# motor_schematic.net
KiCad netlist of a schematic drawn in EAGLE
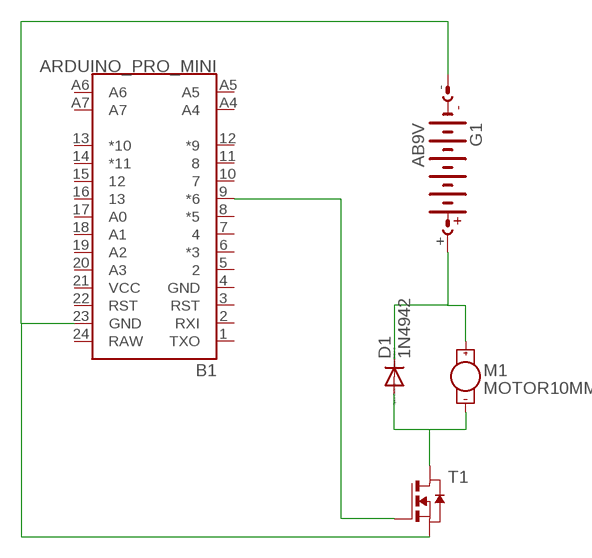
[diagram p0: schematic, sheet 1]

(export (version "E")
  (design (tool "Eeschema 10.0.6"))
  (components
    (comp (ref "B1")
      (value "ARDUINO_PRO_MINI")
      (footprint "eagle-import:ARDUINO_PRO_MINI")
      (libsource (lib "eagle-import") (part "ARDUINO_PRO_MINI"))
    )
    (comp (ref "D1")
      (value "1N4942")
      (footprint "eagle-import:DO41-10")
      (libsource (lib "eagle-import") (part "1N4942"))
    )
    (comp (ref "G1")
      (value "AB9V")
      (footprint "eagle-import:AB9V")
      (libsource (lib "eagle-import") (part "AB9V"))
    )
    (comp (ref "M1")
      (value "MOTOR10MM")
      (footprint "eagle-import:VIBE-MOTOR-10MM")
      (libsource (lib "eagle-import") (part "MOTOR10MM"))
    )
    (comp (ref "T1")
      (value "NMOSSOT23")
      (footprint "eagle-import:SOT-23")
      (libsource (lib "eagle-import") (part "NMOSSOT23"))
    )
  )
  (nets
    (net (code "1") (name "/GND") (class "Default")
      (node (ref "B1") (pin "4") (pinfunction "GND_4") (pintype "power_in"))
    )
    (net (code "2") (name "/RAW") (class "Default")
      (node (ref "B1") (pin "24") (pinfunction "RAW_24") (pintype "power_in"))
    )
    (net (code "3") (name "/VCC") (class "Default")
      (node (ref "B1") (pin "21") (pinfunction "VCC_21") (pintype "power_in"))
    )
    (net (code "4") (name "Net-(B1-*6)") (class "Default")
      (node (ref "B1") (pin "9") (pinfunction "*6_9") (pintype "bidirectional"))
      (node (ref "T1") (pin "3") (pinfunction "G_3") (pintype "passive"))
    )
    (net (code "5") (name "Net-(D1-PadC)") (class "Default")
      (node (ref "D1") (pin "C") (pinfunction "C_C") (pintype "passive"))
      (node (ref "G1") (pin "+") (pinfunction "+_+") (pintype "passive"))
      (node (ref "M1") (pin "+") (pinfunction "+_+") (pintype "bidirectional"))
    )
    (net (code "6") (name "Net-(T1-D)") (class "Default")
      (node (ref "D1") (pin "A") (pinfunction "A_A") (pintype "passive"))
      (node (ref "M1") (pin "-") (pinfunction "-_-") (pintype "bidirectional"))
      (node (ref "T1") (pin "1") (pinfunction "D_1") (pintype "passive"))
    )
    (net (code "7") (name "Net-(T1-S)") (class "Default")
      (node (ref "B1") (pin "23") (pinfunction "GND_23") (pintype "power_in"))
      (node (ref "G1") (pin "-") (pinfunction "-_-") (pintype "passive"))
      (node (ref "T1") (pin "2") (pinfunction "S_2") (pintype "passive"))
    )
    (net (code "8") (name "unconnected-(B1-*3-Pad6)") (class "Default")
      (node (ref "B1") (pin "6") (pinfunction "*3_6") (pintype "bidirectional"))
    )
    (net (code "9") (name "unconnected-(B1-*5-Pad8)") (class "Default")
      (node (ref "B1") (pin "8") (pinfunction "*5_8") (pintype "bidirectional"))
    )
    (net (code "10") (name "unconnected-(B1-*9-Pad12)") (class "Default")
      (node (ref "B1") (pin "12") (pinfunction "*9_12") (pintype "bidirectional"))
    )
    (net (code "11") (name "unconnected-(B1-*10-Pad13)") (class "Default")
      (node (ref "B1") (pin "13") (pinfunction "*10_13") (pintype "bidirectional"))
    )
    (net (code "12") (name "unconnected-(B1-*11-Pad14)") (class "Default")
      (node (ref "B1") (pin "14") (pinfunction "*11_14") (pintype "bidirectional"))
    )
    (net (code "13") (name "unconnected-(B1-2-Pad5)") (class "Default")
      (node (ref "B1") (pin "5") (pinfunction "2_5") (pintype "bidirectional"))
    )
    (net (code "14") (name "unconnected-(B1-4-Pad7)") (class "Default")
      (node (ref "B1") (pin "7") (pinfunction "4_7") (pintype "bidirectional"))
    )
    (net (code "15") (name "unconnected-(B1-7-Pad10)") (class "Default")
      (node (ref "B1") (pin "10") (pinfunction "7_10") (pintype "bidirectional"))
    )
    (net (code "16") (name "unconnected-(B1-8-Pad11)") (class "Default")
      (node (ref "B1") (pin "11") (pinfunction "8_11") (pintype "bidirectional"))
    )
    (net (code "17") (name "unconnected-(B1-12-Pad15)") (class "Default")
      (node (ref "B1") (pin "15") (pinfunction "12_15") (pintype "bidirectional"))
    )
    (net (code "18") (name "unconnected-(B1-13-Pad16)") (class "Default")
      (node (ref "B1") (pin "16") (pinfunction "13_16") (pintype "bidirectional"))
    )
    (net (code "19") (name "unconnected-(B1-A0-Pad17)") (class "Default")
      (node (ref "B1") (pin "17") (pinfunction "A0_17") (pintype "bidirectional"))
    )
    (net (code "20") (name "unconnected-(B1-A1-Pad18)") (class "Default")
      (node (ref "B1") (pin "18") (pinfunction "A1_18") (pintype "bidirectional"))
    )
    (net (code "21") (name "unconnected-(B1-A2-Pad19)") (class "Default")
      (node (ref "B1") (pin "19") (pinfunction "A2_19") (pintype "bidirectional"))
    )
    (net (code "22") (name "unconnected-(B1-A3-Pad20)") (class "Default")
      (node (ref "B1") (pin "20") (pinfunction "A3_20") (pintype "bidirectional"))
    )
    (net (code "23") (name "unconnected-(B1-PadA4)") (class "Default")
      (node (ref "B1") (pin "A4") (pinfunction "A4_A4") (pintype "bidirectional"))
    )
    (net (code "24") (name "unconnected-(B1-PadA5)") (class "Default")
      (node (ref "B1") (pin "A5") (pinfunction "A5_A5") (pintype "bidirectional"))
    )
    (net (code "25") (name "unconnected-(B1-PadA6)") (class "Default")
      (node (ref "B1") (pin "A6") (pinfunction "A6_A6") (pintype "bidirectional"))
    )
    (net (code "26") (name "unconnected-(B1-PadA7)") (class "Default")
      (node (ref "B1") (pin "A7") (pinfunction "A7_A7") (pintype "bidirectional"))
    )
    (net (code "27") (name "unconnected-(B1-RST-Pad3)") (class "Default")
      (node (ref "B1") (pin "3") (pinfunction "RST_3") (pintype "bidirectional"))
    )
    (net (code "28") (name "unconnected-(B1-RST-Pad22)") (class "Default")
      (node (ref "B1") (pin "22") (pinfunction "RST_22") (pintype "bidirectional"))
    )
    (net (code "29") (name "unconnected-(B1-RXI-Pad2)") (class "Default")
      (node (ref "B1") (pin "2") (pinfunction "RXI_2") (pintype "bidirectional"))
    )
    (net (code "30") (name "unconnected-(B1-TXO-Pad1)") (class "Default")
      (node (ref "B1") (pin "1") (pinfunction "TXO_1") (pintype "bidirectional"))
    )
  )
)
